# SAME54-board.net
KiCad netlist of a schematic drawn in EAGLE
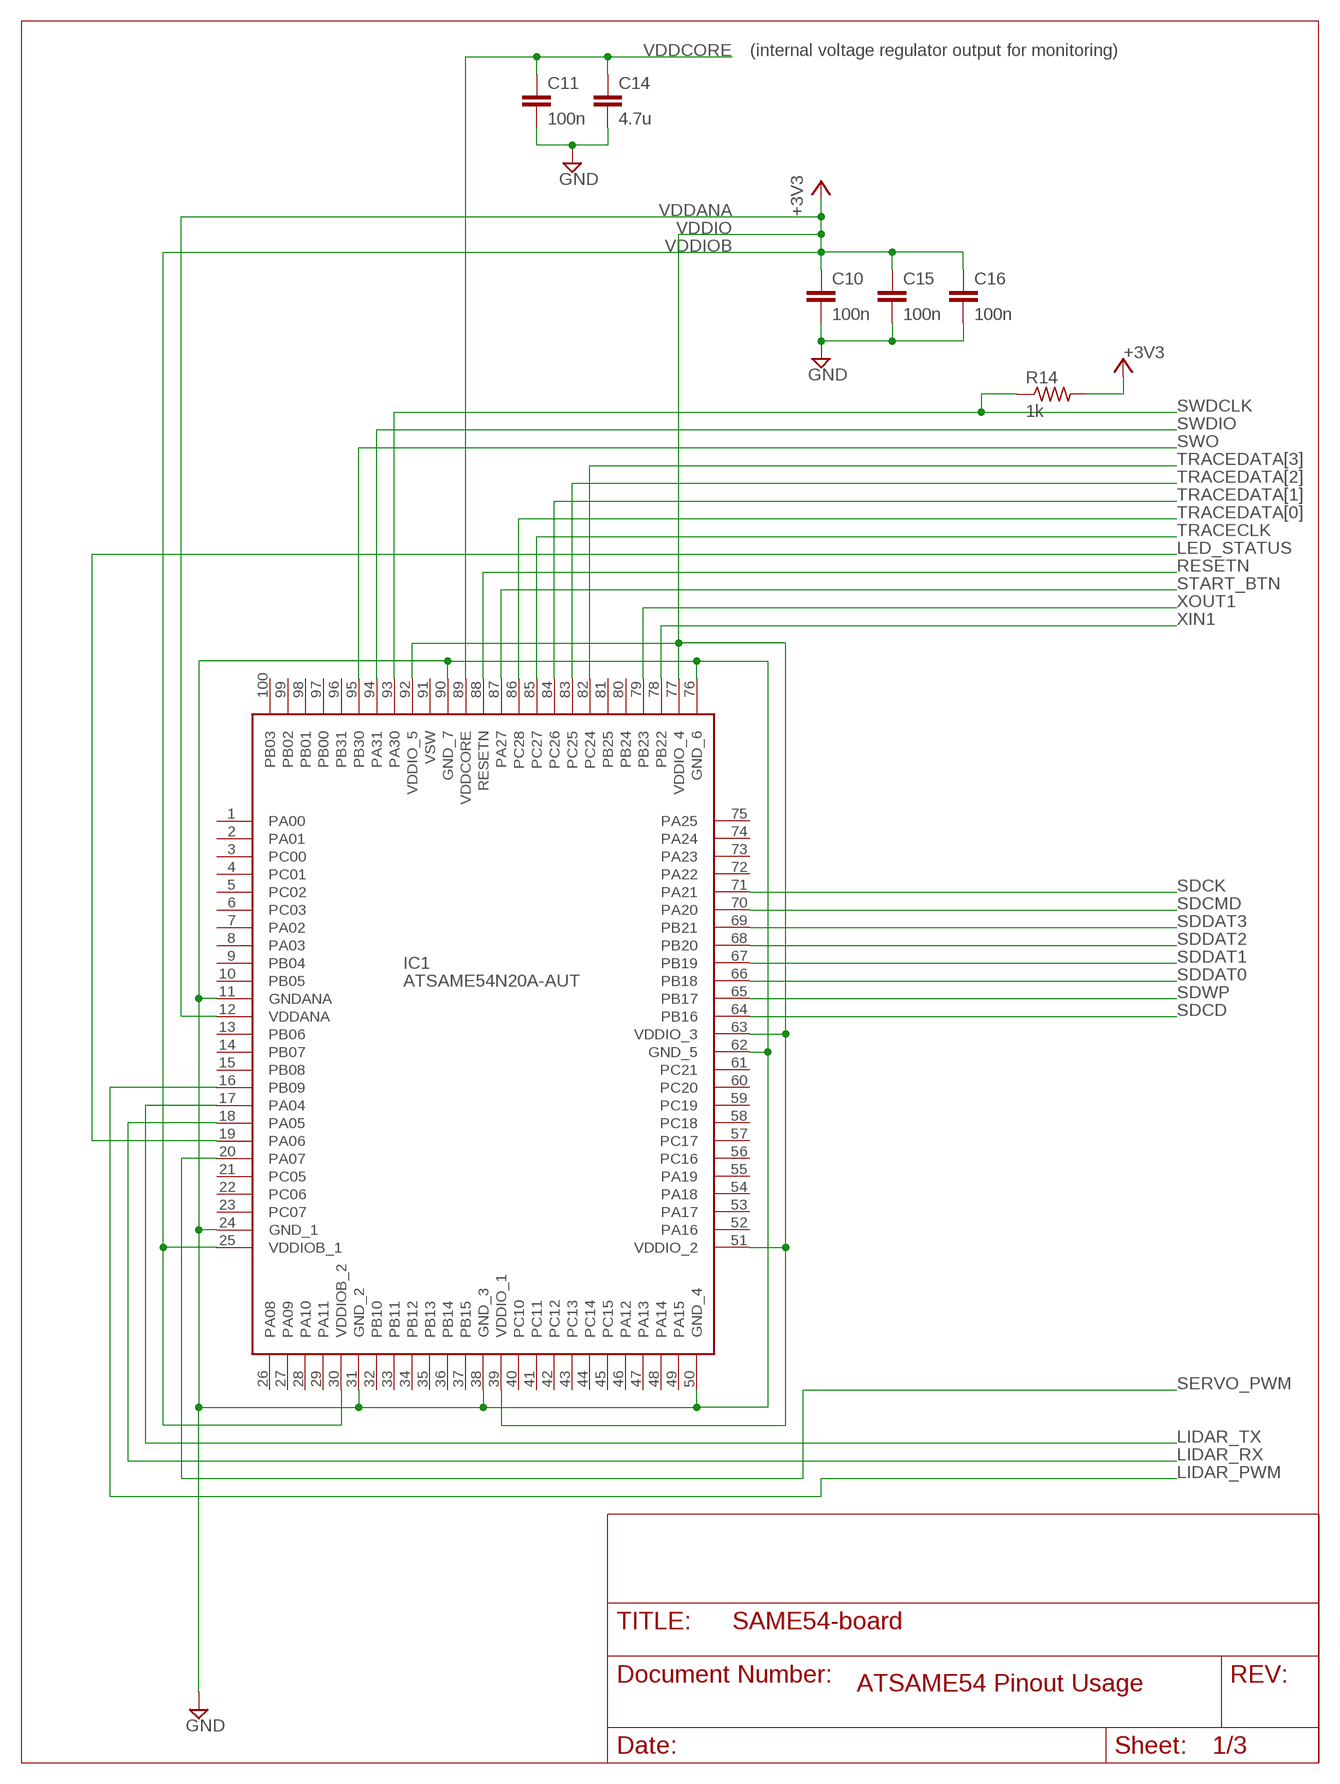
[diagram p0: schematic, sheet 1]
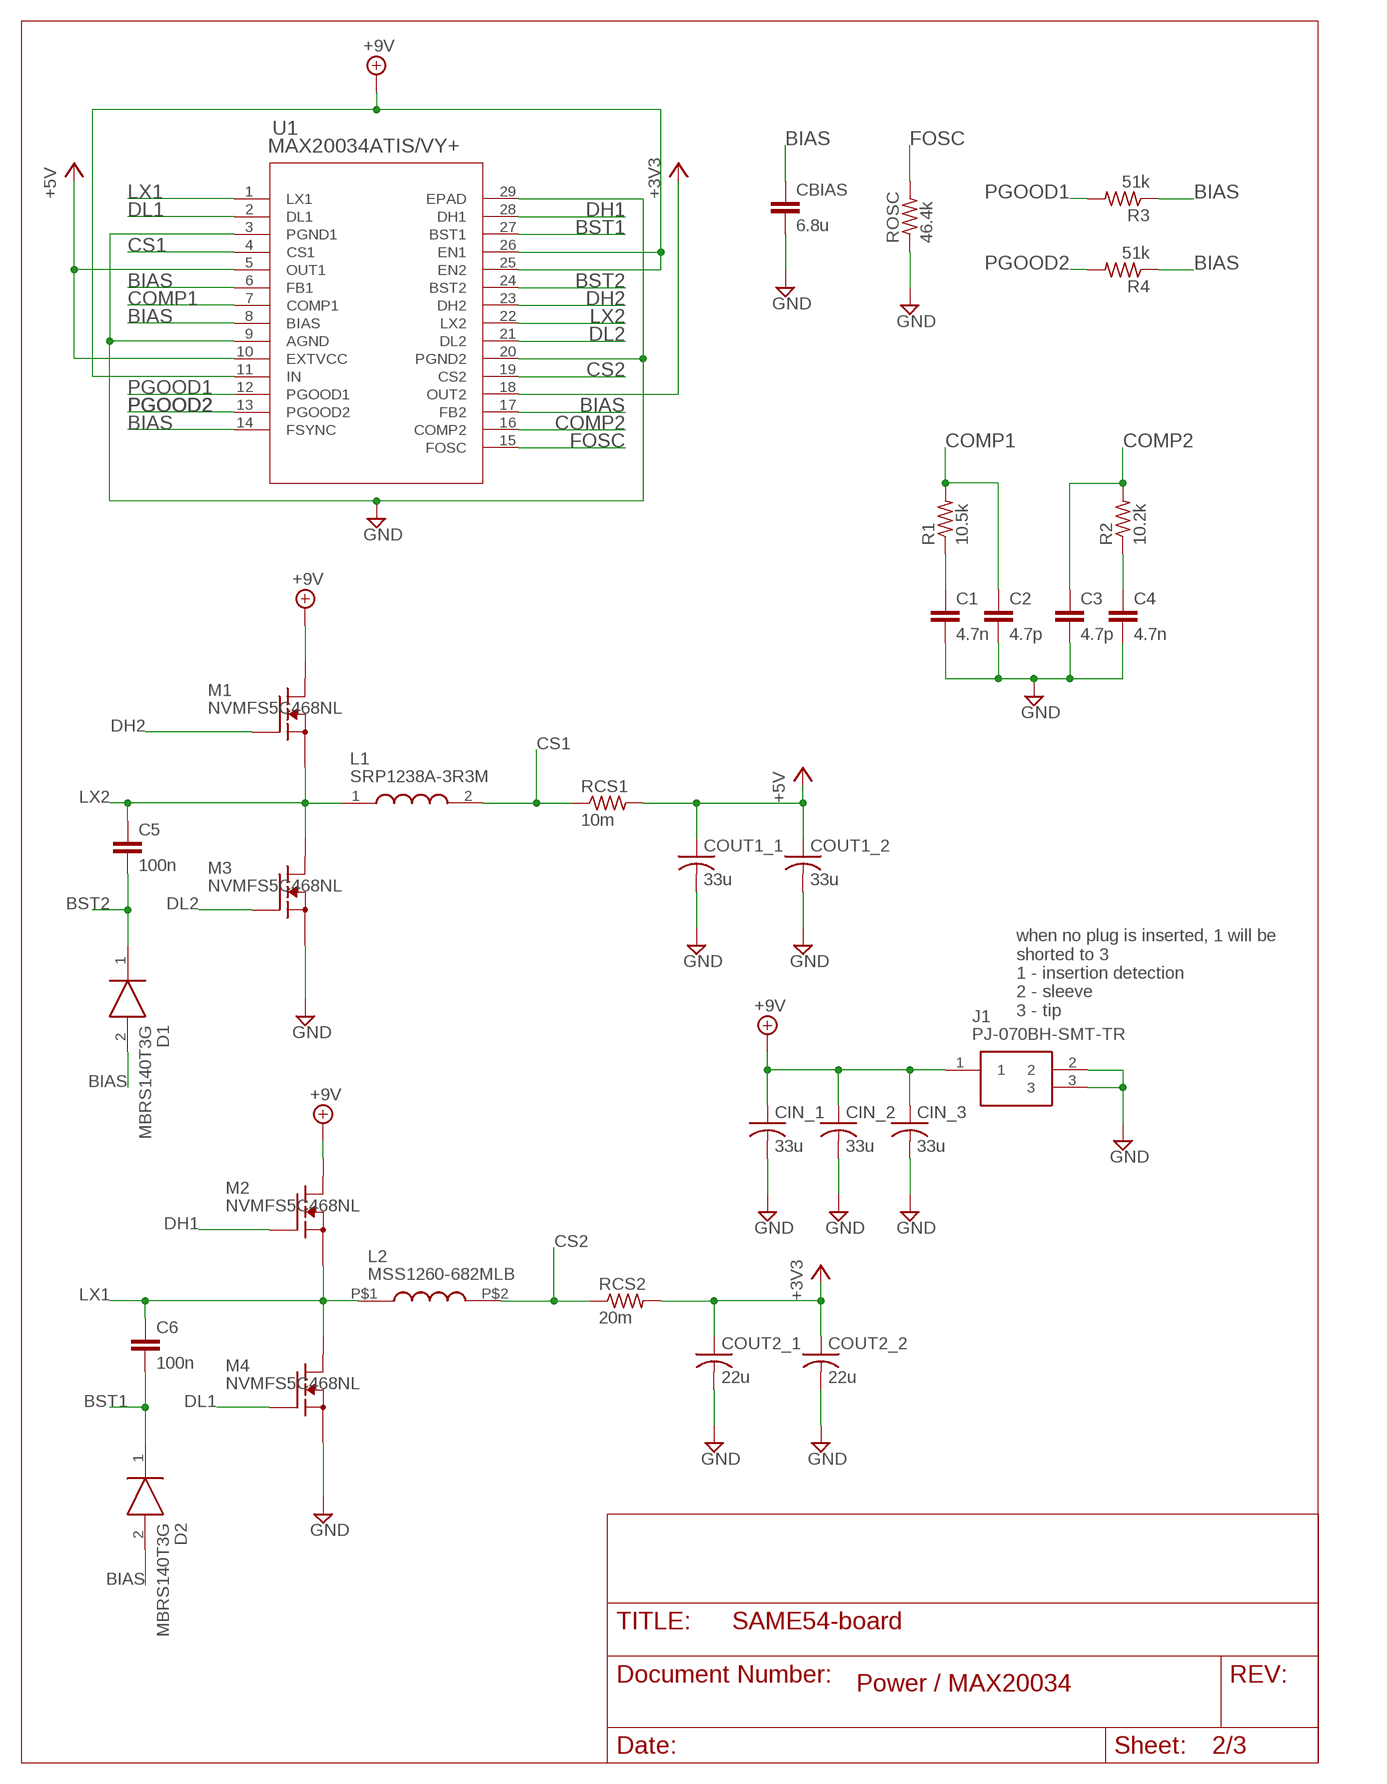
[diagram p1: schematic, sheet 2]
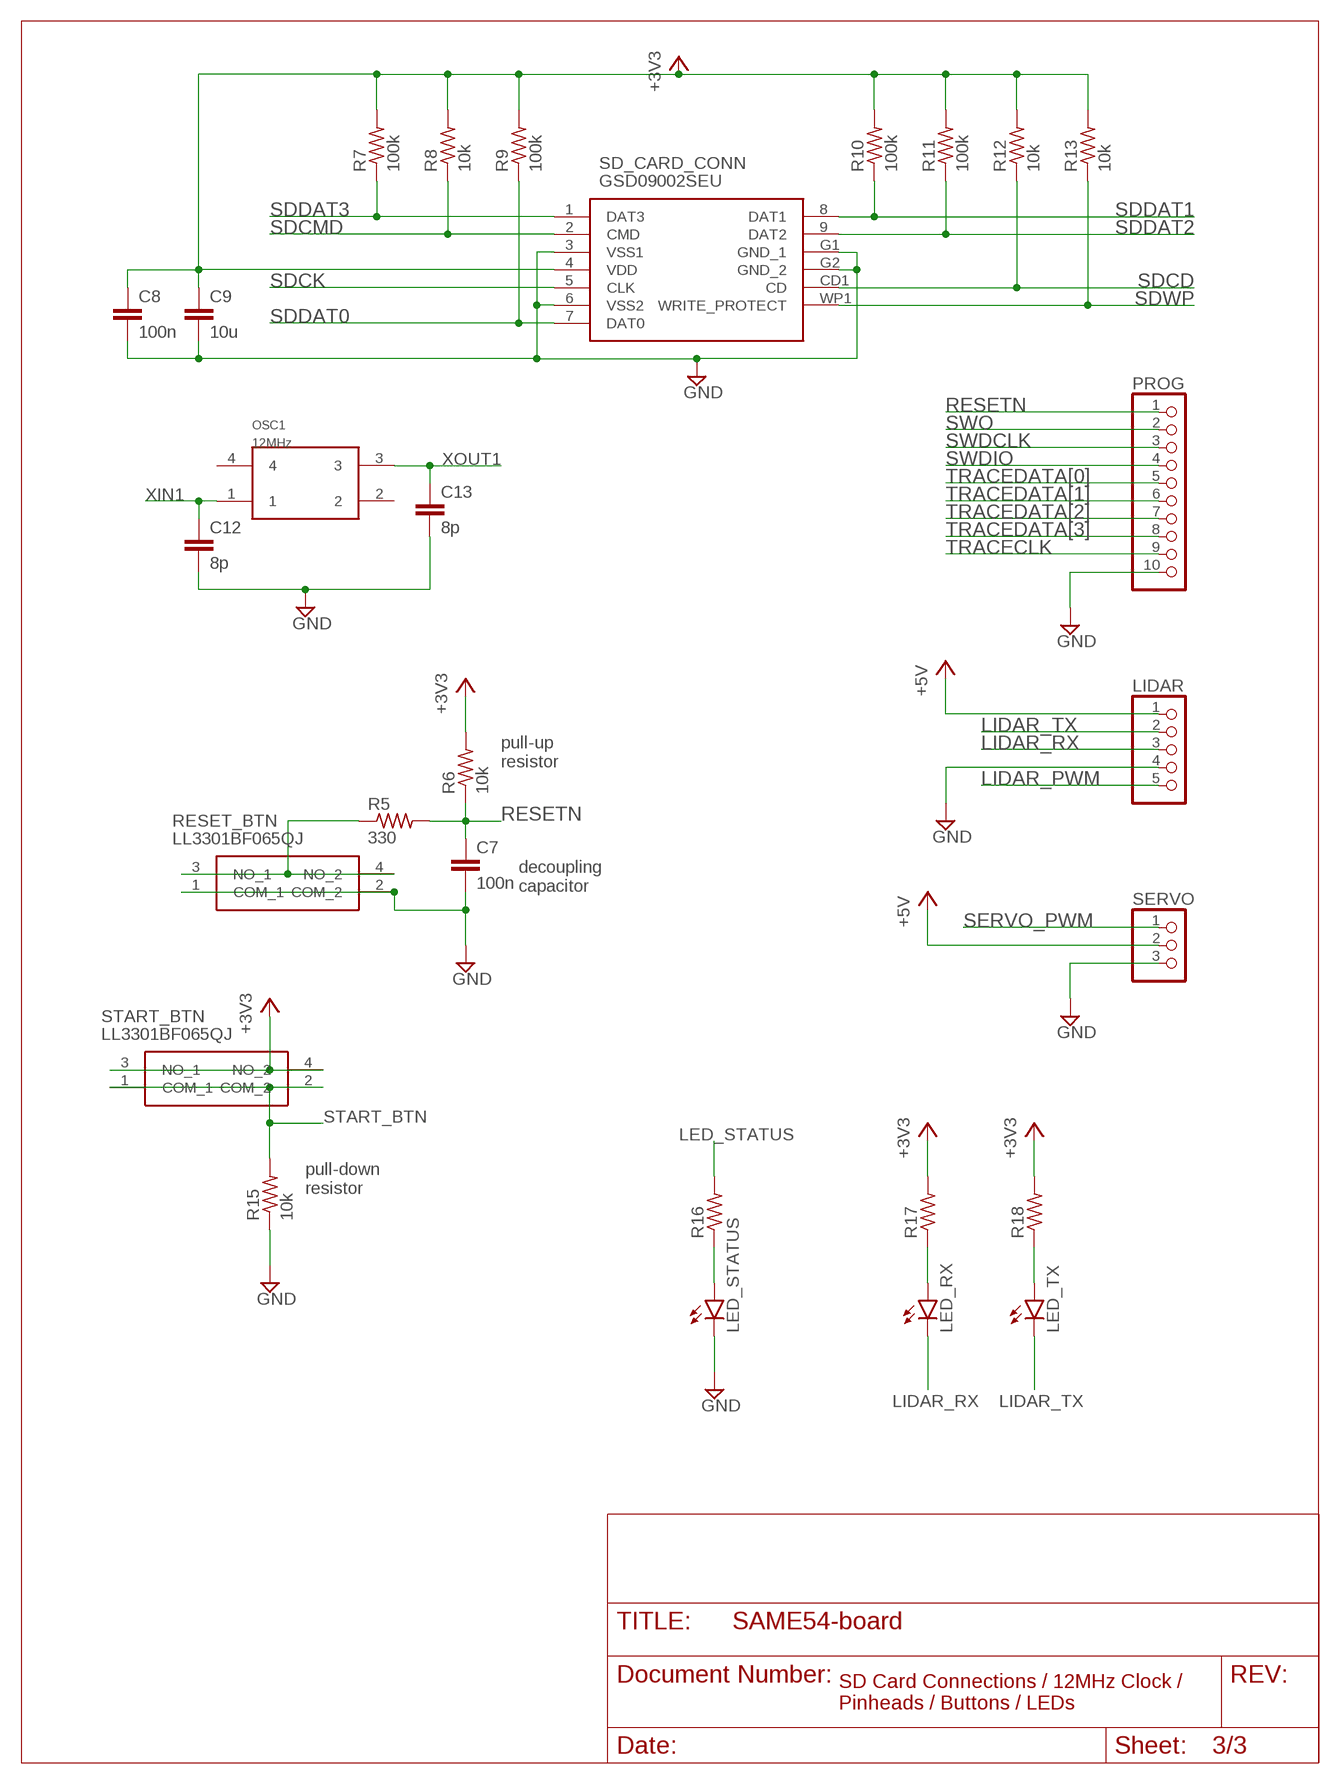
[diagram p2: schematic, sheet 3]

(export (version "E")
  (design (tool "Eeschema 10.0.6"))
  (components
    (comp (ref "C10")
      (value "100n")
      (footprint "eagle-import:C0603")
      (libsource (lib "eagle-import") (part "C-EUC0603"))
    )
    (comp (ref "C11")
      (value "100n")
      (footprint "eagle-import:C0603")
      (libsource (lib "eagle-import") (part "C-EUC0603"))
    )
    (comp (ref "C14")
      (value "4.7u")
      (footprint "eagle-import:C0603")
      (libsource (lib "eagle-import") (part "C-EUC0603"))
    )
    (comp (ref "C15")
      (value "100n")
      (footprint "eagle-import:C0603")
      (libsource (lib "eagle-import") (part "C-EUC0603"))
    )
    (comp (ref "C16")
      (value "100n")
      (footprint "eagle-import:C0603")
      (libsource (lib "eagle-import") (part "C-EUC0603"))
    )
    (comp (ref "IC1")
      (value "ATSAME54N20A-AUT")
      (footprint "eagle-import:QFP50P1600X1600X120-100N")
      (fields (field (name "MOUSER_PART_NUMBER") "556-ATSAME54N20AAUT"))
      (libsource (lib "eagle-import") (part "ATSAME54N20A-AUT"))
    )
    (comp (ref "R14")
      (value "1k")
      (footprint "eagle-import:R0603")
      (libsource (lib "eagle-import") (part "R-US_R0603"))
    )
    (comp (ref "C1")
      (value "4.7n")
      (footprint "eagle-import:C0603")
      (libsource (lib "eagle-import") (part "C-EUC0603"))
    )
    (comp (ref "C2")
      (value "4.7p")
      (footprint "eagle-import:C0402")
      (libsource (lib "eagle-import") (part "C-EUC0402"))
    )
    (comp (ref "C3")
      (value "4.7p")
      (footprint "eagle-import:C0402")
      (libsource (lib "eagle-import") (part "C-EUC0402"))
    )
    (comp (ref "C4")
      (value "4.7n")
      (footprint "eagle-import:C0603")
      (libsource (lib "eagle-import") (part "C-EUC0603"))
    )
    (comp (ref "C5")
      (value "100n")
      (footprint "eagle-import:C0603")
      (libsource (lib "eagle-import") (part "C-EUC0603"))
    )
    (comp (ref "C6")
      (value "100n")
      (footprint "eagle-import:C0603")
      (libsource (lib "eagle-import") (part "C-EUC0603"))
    )
    (comp (ref "CBIAS")
      (value "6.8u")
      (footprint "eagle-import:C1206")
      (libsource (lib "eagle-import") (part "C-EUC1206"))
    )
    (comp (ref "CIN_1")
      (value "33u")
      (footprint "eagle-import:C1812")
      (libsource (lib "eagle-import") (part "C-USC1812"))
    )
    (comp (ref "CIN_2")
      (value "33u")
      (footprint "eagle-import:C1812")
      (libsource (lib "eagle-import") (part "C-USC1812"))
    )
    (comp (ref "CIN_3")
      (value "33u")
      (footprint "eagle-import:C1812")
      (libsource (lib "eagle-import") (part "C-USC1812"))
    )
    (comp (ref "COUT1_1")
      (value "33u")
      (footprint "eagle-import:C1812")
      (libsource (lib "eagle-import") (part "C-USC1812"))
    )
    (comp (ref "COUT1_2")
      (value "33u")
      (footprint "eagle-import:C1812")
      (libsource (lib "eagle-import") (part "C-USC1812"))
    )
    (comp (ref "COUT2_1")
      (value "22u")
      (footprint "eagle-import:C1206")
      (libsource (lib "eagle-import") (part "C-USC1206"))
    )
    (comp (ref "COUT2_2")
      (value "22u")
      (footprint "eagle-import:C1206")
      (libsource (lib "eagle-import") (part "C-USC1206"))
    )
    (comp (ref "D1")
      (value "MBRS140T3G")
      (footprint "eagle-import:DIOM5436X247N")
      (fields (field (name "MOUSER_PART_NUMBER") "863-MBRS140T3G"))
      (libsource (lib "eagle-import") (part "MBRS140T3G"))
    )
    (comp (ref "D2")
      (value "MBRS140T3G")
      (footprint "eagle-import:DIOM5436X247N")
      (fields (field (name "MOUSER_PART_NUMBER") "863-MBRS140T3G"))
      (libsource (lib "eagle-import") (part "MBRS140T3G"))
    )
    (comp (ref "J1")
      (value "PJ-070BH-SMT-TR")
      (footprint "eagle-import:PJ070BHSMTTR")
      (fields (field (name "MOUSER_PART_NUMBER") "490-PJ-070BH-SMT-TR"))
      (libsource (lib "eagle-import") (part "PJ-070BH-SMT-TR"))
    )
    (comp (ref "L1")
      (value "SRP1238A-3R3M")
      (footprint "eagle-import:INDPM135125X350N")
      (fields (field (name "MOUSER_PART_NUMBER") "652-SRP1238A-3R3M"))
      (libsource (lib "eagle-import") (part "SRP1238A-3R3M"))
    )
    (comp (ref "L2")
      (value "MSS1260-682MLB")
      (footprint "eagle-import:MSS1260")
      (libsource (lib "eagle-import") (part "MSS1260-682MLB"))
    )
    (comp (ref "M1")
      (value "NVMFS5C468NL")
      (footprint "eagle-import:DFN5_SO-8FL")
      (libsource (lib "eagle-import") (part "NVMFS5C468NL"))
    )
    (comp (ref "M2")
      (value "NVMFS5C468NL")
      (footprint "eagle-import:DFN5_SO-8FL")
      (libsource (lib "eagle-import") (part "NVMFS5C468NL"))
    )
    (comp (ref "M3")
      (value "NVMFS5C468NL")
      (footprint "eagle-import:DFN5_SO-8FL")
      (libsource (lib "eagle-import") (part "NVMFS5C468NL"))
    )
    (comp (ref "M4")
      (value "NVMFS5C468NL")
      (footprint "eagle-import:DFN5_SO-8FL")
      (libsource (lib "eagle-import") (part "NVMFS5C468NL"))
    )
    (comp (ref "R1")
      (value "10.5k")
      (footprint "eagle-import:R0402")
      (libsource (lib "eagle-import") (part "R-US_R0402"))
    )
    (comp (ref "R2")
      (value "10.2k")
      (footprint "eagle-import:R0402")
      (libsource (lib "eagle-import") (part "R-US_R0402"))
    )
    (comp (ref "R3")
      (value "51k")
      (footprint "eagle-import:R0402")
      (libsource (lib "eagle-import") (part "R-US_R0402"))
    )
    (comp (ref "R4")
      (value "51k")
      (footprint "eagle-import:R0402")
      (libsource (lib "eagle-import") (part "R-US_R0402"))
    )
    (comp (ref "RCS1")
      (value "10m")
      (footprint "eagle-import:R0603")
      (libsource (lib "eagle-import") (part "R-US_R0603"))
    )
    (comp (ref "RCS2")
      (value "20m")
      (footprint "eagle-import:R1206")
      (libsource (lib "eagle-import") (part "R-US_R1206"))
    )
    (comp (ref "ROSC")
      (value "46.4k")
      (footprint "eagle-import:R0402")
      (libsource (lib "eagle-import") (part "R-US_R0402"))
    )
    (comp (ref "U1")
      (value "MAX20034ATIS/VY+")
      (footprint "eagle-import:21-100130_MXM")
      (fields (field (name "MANUFACTURER_PART_NUMBER") "MAX20034ATISVY+"))
      (libsource (lib "eagle-import") (part "MAX20034ATIS/VY+"))
    )
    (comp (ref "C7")
      (value "100n")
      (footprint "eagle-import:C0603")
      (libsource (lib "eagle-import") (part "C-EUC0603"))
    )
    (comp (ref "C8")
      (value "100n")
      (footprint "eagle-import:C0603")
      (libsource (lib "eagle-import") (part "C-EUC0603"))
    )
    (comp (ref "C9")
      (value "10u")
      (footprint "eagle-import:C0603")
      (libsource (lib "eagle-import") (part "C-EUC0603"))
    )
    (comp (ref "C12")
      (value "8p")
      (footprint "eagle-import:C0603")
      (libsource (lib "eagle-import") (part "C-EUC0603"))
    )
    (comp (ref "C13")
      (value "8p")
      (footprint "eagle-import:C0603")
      (libsource (lib "eagle-import") (part "C-EUC0603"))
    )
    (comp (ref "LED_RX")
      (value "LEDCHIPLED_0603")
      (footprint "eagle-import:CHIPLED_0603")
      (libsource (lib "eagle-import") (part "LEDCHIPLED_0603"))
    )
    (comp (ref "LED_STATUS")
      (value "LEDCHIPLED_0603")
      (footprint "eagle-import:CHIPLED_0603")
      (libsource (lib "eagle-import") (part "LEDCHIPLED_0603"))
    )
    (comp (ref "LED_TX")
      (value "LEDCHIPLED_0603")
      (footprint "eagle-import:CHIPLED_0603")
      (libsource (lib "eagle-import") (part "LEDCHIPLED_0603"))
    )
    (comp (ref "LIDAR")
      (value "PINHD-1X5")
      (footprint "eagle-import:1X05")
      (libsource (lib "eagle-import") (part "PINHD-1X5"))
    )
    (comp (ref "OSC1")
      (value "CX3225CA12000D0KPSC1CX3225CA")
      (footprint "eagle-import:OSCCC320X250X90N")
      (libsource (lib "eagle-import") (part "CX3225CA12000D0KPSC1CX3225CA"))
    )
    (comp (ref "PROG")
      (value "PINHD-1X10")
      (footprint "eagle-import:1X10")
      (libsource (lib "eagle-import") (part "PINHD-1X10"))
    )
    (comp (ref "R5")
      (value "330")
      (footprint "eagle-import:R0603")
      (libsource (lib "eagle-import") (part "R-US_R0603"))
    )
    (comp (ref "R6")
      (value "10k")
      (footprint "eagle-import:R0603")
      (libsource (lib "eagle-import") (part "R-US_R0603"))
    )
    (comp (ref "R7")
      (value "100k")
      (footprint "eagle-import:R0603")
      (libsource (lib "eagle-import") (part "R-US_R0603"))
    )
    (comp (ref "R8")
      (value "10k")
      (footprint "eagle-import:R0603")
      (libsource (lib "eagle-import") (part "R-US_R0603"))
    )
    (comp (ref "R9")
      (value "100k")
      (footprint "eagle-import:R0603")
      (libsource (lib "eagle-import") (part "R-US_R0603"))
    )
    (comp (ref "R10")
      (value "100k")
      (footprint "eagle-import:R0603")
      (libsource (lib "eagle-import") (part "R-US_R0603"))
    )
    (comp (ref "R11")
      (value "100k")
      (footprint "eagle-import:R0603")
      (libsource (lib "eagle-import") (part "R-US_R0603"))
    )
    (comp (ref "R12")
      (value "10k")
      (footprint "eagle-import:R0603")
      (libsource (lib "eagle-import") (part "R-US_R0603"))
    )
    (comp (ref "R13")
      (value "10k")
      (footprint "eagle-import:R0603")
      (libsource (lib "eagle-import") (part "R-US_R0603"))
    )
    (comp (ref "R15")
      (value "10k")
      (footprint "eagle-import:R0603")
      (libsource (lib "eagle-import") (part "R-US_R0603"))
    )
    (comp (ref "R16")
      (value "R-US_R0603")
      (footprint "eagle-import:R0603")
      (libsource (lib "eagle-import") (part "R-US_R0603"))
    )
    (comp (ref "R17")
      (value "R-US_R0603")
      (footprint "eagle-import:R0603")
      (libsource (lib "eagle-import") (part "R-US_R0603"))
    )
    (comp (ref "R18")
      (value "R-US_R0603")
      (footprint "eagle-import:R0603")
      (libsource (lib "eagle-import") (part "R-US_R0603"))
    )
    (comp (ref "RESET_BTN")
      (value "LL3301BF065QJ")
      (footprint "eagle-import:LL3301BF065QJ")
      (fields (field (name "MOUSER_PART_NUMBER") "612-LL3301BF065QJ"))
      (libsource (lib "eagle-import") (part "LL3301BF065QJ"))
    )
    (comp (ref "SD_CARD_CONN")
      (value "GSD09002SEU")
      (footprint "eagle-import:GSD09002SEU")
      (fields (field (name "MOUSER_PART_NUMBER") "523-GSD09002SEU"))
      (libsource (lib "eagle-import") (part "GSD09002SEU"))
    )
    (comp (ref "SERVO")
      (value "PINHD-1X3")
      (footprint "eagle-import:1X03")
      (libsource (lib "eagle-import") (part "PINHD-1X3"))
    )
    (comp (ref "START_BTN")
      (value "LL3301BF065QJ")
      (footprint "eagle-import:LL3301BF065QJ")
      (fields (field (name "MOUSER_PART_NUMBER") "612-LL3301BF065QJ"))
      (libsource (lib "eagle-import") (part "LL3301BF065QJ"))
    )
  )
  (nets
    (net (code "1") (name "+3V3") (class "Default")
      (node (ref "C10") (pin "1") (pinfunction "1_1") (pintype "passive"))
      (node (ref "C15") (pin "1") (pinfunction "1_1") (pintype "passive"))
      (node (ref "C16") (pin "1") (pinfunction "1_1") (pintype "passive"))
      (node (ref "C8") (pin "1") (pinfunction "1_1") (pintype "passive"))
      (node (ref "C9") (pin "1") (pinfunction "1_1") (pintype "passive"))
      (node (ref "COUT2_1") (pin "1") (pinfunction "1_1") (pintype "passive"))
      (node (ref "COUT2_2") (pin "1") (pinfunction "1_1") (pintype "passive"))
      (node (ref "IC1") (pin "12") (pinfunction "VDDANA_12") (pintype "bidirectional"))
      (node (ref "IC1") (pin "25") (pinfunction "VDDIOB_1_25") (pintype "bidirectional"))
      (node (ref "IC1") (pin "30") (pinfunction "VDDIOB_2_30") (pintype "bidirectional"))
      (node (ref "IC1") (pin "39") (pinfunction "VDDIO_1_39") (pintype "bidirectional"))
      (node (ref "IC1") (pin "51") (pinfunction "VDDIO_2_51") (pintype "bidirectional"))
      (node (ref "IC1") (pin "63") (pinfunction "VDDIO_3_63") (pintype "bidirectional"))
      (node (ref "IC1") (pin "77") (pinfunction "VDDIO_4_77") (pintype "bidirectional"))
      (node (ref "IC1") (pin "92") (pinfunction "VDDIO_5_92") (pintype "bidirectional"))
      (node (ref "R10") (pin "2") (pinfunction "2_2") (pintype "passive"))
      (node (ref "R11") (pin "2") (pinfunction "2_2") (pintype "passive"))
      (node (ref "R12") (pin "2") (pinfunction "2_2") (pintype "passive"))
      (node (ref "R13") (pin "2") (pinfunction "2_2") (pintype "passive"))
      (node (ref "R14") (pin "2") (pinfunction "2_2") (pintype "passive"))
      (node (ref "R17") (pin "2") (pinfunction "2_2") (pintype "passive"))
      (node (ref "R18") (pin "2") (pinfunction "2_2") (pintype "passive"))
      (node (ref "R6") (pin "2") (pinfunction "2_2") (pintype "passive"))
      (node (ref "R7") (pin "2") (pinfunction "2_2") (pintype "passive"))
      (node (ref "R8") (pin "2") (pinfunction "2_2") (pintype "passive"))
      (node (ref "R9") (pin "2") (pinfunction "2_2") (pintype "passive"))
      (node (ref "RCS2") (pin "2") (pinfunction "2_2") (pintype "passive"))
      (node (ref "SD_CARD_CONN") (pin "4") (pinfunction "VDD_4") (pintype "bidirectional"))
      (node (ref "START_BTN") (pin "3") (pinfunction "NO_1_3") (pintype "bidirectional"))
      (node (ref "START_BTN") (pin "4") (pinfunction "NO_2_4") (pintype "bidirectional"))
      (node (ref "U1") (pin "18") (pinfunction "OUT2_18") (pintype "output"))
    )
    (net (code "2") (name "+5V") (class "Default")
      (node (ref "COUT1_1") (pin "1") (pinfunction "1_1") (pintype "passive"))
      (node (ref "COUT1_2") (pin "1") (pinfunction "1_1") (pintype "passive"))
      (node (ref "LIDAR") (pin "1") (pinfunction "1_1") (pintype "passive"))
      (node (ref "RCS1") (pin "2") (pinfunction "2_2") (pintype "passive"))
      (node (ref "SERVO") (pin "2") (pinfunction "2_2") (pintype "passive"))
      (node (ref "U1") (pin "10") (pinfunction "EXTVCC_10") (pintype "input"))
      (node (ref "U1") (pin "5") (pinfunction "OUT1_5") (pintype "output"))
    )
    (net (code "3") (name "+9V") (class "Default")
      (node (ref "CIN_1") (pin "1") (pinfunction "1_1") (pintype "passive"))
      (node (ref "CIN_2") (pin "1") (pinfunction "1_1") (pintype "passive"))
      (node (ref "CIN_3") (pin "1") (pinfunction "1_1") (pintype "passive"))
      (node (ref "J1") (pin "1") (pinfunction "1_1") (pintype "bidirectional"))
      (node (ref "M1") (pin "D1") (pinfunction "D_D1") (pintype "passive"))
      (node (ref "M1") (pin "D2") (pinfunction "D_D2") (pintype "passive"))
      (node (ref "M1") (pin "D3") (pinfunction "D_D3") (pintype "passive"))
      (node (ref "M1") (pin "D4") (pinfunction "D_D4") (pintype "passive"))
      (node (ref "M2") (pin "D1") (pinfunction "D_D1") (pintype "passive"))
      (node (ref "M2") (pin "D2") (pinfunction "D_D2") (pintype "passive"))
      (node (ref "M2") (pin "D3") (pinfunction "D_D3") (pintype "passive"))
      (node (ref "M2") (pin "D4") (pinfunction "D_D4") (pintype "passive"))
      (node (ref "U1") (pin "11") (pinfunction "IN_11") (pintype "input"))
      (node (ref "U1") (pin "25") (pinfunction "EN2_25") (pintype "input"))
      (node (ref "U1") (pin "26") (pinfunction "EN1_26") (pintype "input"))
    )
    (net (code "4") (name "BIAS") (class "Default")
      (node (ref "CBIAS") (pin "1") (pinfunction "1_1") (pintype "passive"))
      (node (ref "D1") (pin "2") (pinfunction "A_2") (pintype "bidirectional"))
      (node (ref "D2") (pin "2") (pinfunction "A_2") (pintype "bidirectional"))
      (node (ref "R3") (pin "1") (pinfunction "1_1") (pintype "passive"))
      (node (ref "R4") (pin "1") (pinfunction "1_1") (pintype "passive"))
      (node (ref "U1") (pin "14") (pinfunction "FSYNC_14") (pintype "input"))
      (node (ref "U1") (pin "17") (pinfunction "FB2_17") (pintype "input"))
      (node (ref "U1") (pin "6") (pinfunction "FB1_6") (pintype "input"))
      (node (ref "U1") (pin "8") (pinfunction "BIAS_8") (pintype "output"))
    )
    (net (code "5") (name "BST1") (class "Default")
      (node (ref "C6") (pin "2") (pinfunction "2_2") (pintype "passive"))
      (node (ref "D2") (pin "1") (pinfunction "K_1") (pintype "bidirectional"))
      (node (ref "U1") (pin "27") (pinfunction "BST1_27") (pintype "passive"))
    )
    (net (code "6") (name "BST2") (class "Default")
      (node (ref "C5") (pin "2") (pinfunction "2_2") (pintype "passive"))
      (node (ref "D1") (pin "1") (pinfunction "K_1") (pintype "bidirectional"))
      (node (ref "U1") (pin "24") (pinfunction "BST2_24") (pintype "passive"))
    )
    (net (code "7") (name "COMP1") (class "Default")
      (node (ref "C2") (pin "1") (pinfunction "1_1") (pintype "passive"))
      (node (ref "R1") (pin "2") (pinfunction "2_2") (pintype "passive"))
      (node (ref "U1") (pin "7") (pinfunction "COMP1_7") (pintype "output"))
    )
    (net (code "8") (name "COMP2") (class "Default")
      (node (ref "C3") (pin "1") (pinfunction "1_1") (pintype "passive"))
      (node (ref "R2") (pin "2") (pinfunction "2_2") (pintype "passive"))
      (node (ref "U1") (pin "16") (pinfunction "COMP2_16") (pintype "output"))
    )
    (net (code "9") (name "CS1") (class "Default")
      (node (ref "L1") (pin "2") (pinfunction "2_2") (pintype "bidirectional"))
      (node (ref "RCS1") (pin "1") (pinfunction "1_1") (pintype "passive"))
      (node (ref "U1") (pin "4") (pinfunction "CS1_4") (pintype "input"))
    )
    (net (code "10") (name "CS2") (class "Default")
      (node (ref "L2") (pin "P$2") (pinfunction "2_P$2") (pintype "bidirectional"))
      (node (ref "RCS2") (pin "1") (pinfunction "1_1") (pintype "passive"))
      (node (ref "U1") (pin "19") (pinfunction "CS2_19") (pintype "input"))
    )
    (net (code "11") (name "DH1") (class "Default")
      (node (ref "M2") (pin "G") (pinfunction "G_G") (pintype "passive"))
      (node (ref "U1") (pin "28") (pinfunction "DH1_28") (pintype "output"))
    )
    (net (code "12") (name "DH2") (class "Default")
      (node (ref "M1") (pin "G") (pinfunction "G_G") (pintype "passive"))
      (node (ref "U1") (pin "23") (pinfunction "DH2_23") (pintype "output"))
    )
    (net (code "13") (name "DL1") (class "Default")
      (node (ref "M4") (pin "G") (pinfunction "G_G") (pintype "passive"))
      (node (ref "U1") (pin "2") (pinfunction "DL1_2") (pintype "output"))
    )
    (net (code "14") (name "DL2") (class "Default")
      (node (ref "M3") (pin "G") (pinfunction "G_G") (pintype "passive"))
      (node (ref "U1") (pin "21") (pinfunction "DL2_21") (pintype "output"))
    )
    (net (code "15") (name "FOSC") (class "Default")
      (node (ref "ROSC") (pin "2") (pinfunction "2_2") (pintype "passive"))
      (node (ref "U1") (pin "15") (pinfunction "FOSC_15") (pintype "input"))
    )
    (net (code "16") (name "GND") (class "Default")
      (node (ref "C1") (pin "2") (pinfunction "2_2") (pintype "passive"))
      (node (ref "C10") (pin "2") (pinfunction "2_2") (pintype "passive"))
      (node (ref "C11") (pin "2") (pinfunction "2_2") (pintype "passive"))
      (node (ref "C12") (pin "2") (pinfunction "2_2") (pintype "passive"))
      (node (ref "C13") (pin "2") (pinfunction "2_2") (pintype "passive"))
      (node (ref "C14") (pin "2") (pinfunction "2_2") (pintype "passive"))
      (node (ref "C15") (pin "2") (pinfunction "2_2") (pintype "passive"))
      (node (ref "C16") (pin "2") (pinfunction "2_2") (pintype "passive"))
      (node (ref "C2") (pin "2") (pinfunction "2_2") (pintype "passive"))
      (node (ref "C3") (pin "2") (pinfunction "2_2") (pintype "passive"))
      (node (ref "C4") (pin "2") (pinfunction "2_2") (pintype "passive"))
      (node (ref "C7") (pin "2") (pinfunction "2_2") (pintype "passive"))
      (node (ref "C8") (pin "2") (pinfunction "2_2") (pintype "passive"))
      (node (ref "C9") (pin "2") (pinfunction "2_2") (pintype "passive"))
      (node (ref "CBIAS") (pin "2") (pinfunction "2_2") (pintype "passive"))
      (node (ref "CIN_1") (pin "2") (pinfunction "2_2") (pintype "passive"))
      (node (ref "CIN_2") (pin "2") (pinfunction "2_2") (pintype "passive"))
      (node (ref "CIN_3") (pin "2") (pinfunction "2_2") (pintype "passive"))
      (node (ref "COUT1_1") (pin "2") (pinfunction "2_2") (pintype "passive"))
      (node (ref "COUT1_2") (pin "2") (pinfunction "2_2") (pintype "passive"))
      (node (ref "COUT2_1") (pin "2") (pinfunction "2_2") (pintype "passive"))
      (node (ref "COUT2_2") (pin "2") (pinfunction "2_2") (pintype "passive"))
      (node (ref "IC1") (pin "11") (pinfunction "GNDANA_11") (pintype "bidirectional"))
      (node (ref "IC1") (pin "24") (pinfunction "GND_1_24") (pintype "bidirectional"))
      (node (ref "IC1") (pin "31") (pinfunction "GND_2_31") (pintype "bidirectional"))
      (node (ref "IC1") (pin "38") (pinfunction "GND_3_38") (pintype "bidirectional"))
      (node (ref "IC1") (pin "50") (pinfunction "GND_4_50") (pintype "bidirectional"))
      (node (ref "IC1") (pin "62") (pinfunction "GND_5_62") (pintype "bidirectional"))
      (node (ref "IC1") (pin "76") (pinfunction "GND_6_76") (pintype "bidirectional"))
      (node (ref "IC1") (pin "90") (pinfunction "GND_7_90") (pintype "bidirectional"))
      (node (ref "J1") (pin "2") (pinfunction "2_2") (pintype "bidirectional"))
      (node (ref "J1") (pin "3") (pinfunction "3_3") (pintype "bidirectional"))
      (node (ref "LED_STATUS") (pin "C") (pinfunction "C_C") (pintype "passive"))
      (node (ref "LIDAR") (pin "4") (pinfunction "4_4") (pintype "passive"))
      (node (ref "M3") (pin "S1") (pinfunction "S_S1") (pintype "passive"))
      (node (ref "M3") (pin "S2") (pinfunction "S_S2") (pintype "passive"))
      (node (ref "M3") (pin "S3") (pinfunction "S_S3") (pintype "passive"))
      (node (ref "M4") (pin "S1") (pinfunction "S_S1") (pintype "passive"))
      (node (ref "M4") (pin "S2") (pinfunction "S_S2") (pintype "passive"))
      (node (ref "M4") (pin "S3") (pinfunction "S_S3") (pintype "passive"))
      (node (ref "PROG") (pin "10") (pinfunction "10_10") (pintype "passive"))
      (node (ref "R15") (pin "1") (pinfunction "1_1") (pintype "passive"))
      (node (ref "RESET_BTN") (pin "1") (pinfunction "COM_1_1") (pintype "bidirectional"))
      (node (ref "RESET_BTN") (pin "2") (pinfunction "COM_2_2") (pintype "bidirectional"))
      (node (ref "ROSC") (pin "1") (pinfunction "1_1") (pintype "passive"))
      (node (ref "SD_CARD_CONN") (pin "3") (pinfunction "VSS1_3") (pintype "bidirectional"))
      (node (ref "SD_CARD_CONN") (pin "6") (pinfunction "VSS2_6") (pintype "bidirectional"))
      (node (ref "SD_CARD_CONN") (pin "G1") (pinfunction "GND_1_G1") (pintype "bidirectional"))
      (node (ref "SD_CARD_CONN") (pin "G2") (pinfunction "GND_2_G2") (pintype "bidirectional"))
      (node (ref "SERVO") (pin "3") (pinfunction "3_3") (pintype "passive"))
      (node (ref "U1") (pin "20") (pinfunction "PGND2_20") (pintype "power_in"))
      (node (ref "U1") (pin "29") (pinfunction "EPAD_29") (pintype "power_in"))
      (node (ref "U1") (pin "3") (pinfunction "PGND1_3") (pintype "power_in"))
      (node (ref "U1") (pin "9") (pinfunction "AGND_9") (pintype "power_in"))
    )
    (net (code "17") (name "LED_STATUS") (class "Default")
      (node (ref "IC1") (pin "19") (pinfunction "PA06_19") (pintype "bidirectional"))
      (node (ref "R16") (pin "2") (pinfunction "2_2") (pintype "passive"))
    )
    (net (code "18") (name "LIDAR_PWM") (class "Default")
      (node (ref "IC1") (pin "16") (pinfunction "PB09_16") (pintype "bidirectional"))
      (node (ref "LIDAR") (pin "5") (pinfunction "5_5") (pintype "passive"))
    )
    (net (code "19") (name "LIDAR_RX") (class "Default")
      (node (ref "IC1") (pin "18") (pinfunction "PA05_18") (pintype "bidirectional"))
      (node (ref "LED_RX") (pin "C") (pinfunction "C_C") (pintype "passive"))
      (node (ref "LIDAR") (pin "3") (pinfunction "3_3") (pintype "passive"))
    )
    (net (code "20") (name "LIDAR_TX") (class "Default")
      (node (ref "IC1") (pin "17") (pinfunction "PA04_17") (pintype "bidirectional"))
      (node (ref "LED_TX") (pin "C") (pinfunction "C_C") (pintype "passive"))
      (node (ref "LIDAR") (pin "2") (pinfunction "2_2") (pintype "passive"))
    )
    (net (code "21") (name "LX1") (class "Default")
      (node (ref "C6") (pin "1") (pinfunction "1_1") (pintype "passive"))
      (node (ref "L2") (pin "P$1") (pinfunction "1_P$1") (pintype "bidirectional"))
      (node (ref "M2") (pin "S1") (pinfunction "S_S1") (pintype "passive"))
      (node (ref "M2") (pin "S2") (pinfunction "S_S2") (pintype "passive"))
      (node (ref "M2") (pin "S3") (pinfunction "S_S3") (pintype "passive"))
      (node (ref "M4") (pin "D1") (pinfunction "D_D1") (pintype "passive"))
      (node (ref "M4") (pin "D2") (pinfunction "D_D2") (pintype "passive"))
      (node (ref "M4") (pin "D3") (pinfunction "D_D3") (pintype "passive"))
      (node (ref "M4") (pin "D4") (pinfunction "D_D4") (pintype "passive"))
      (node (ref "U1") (pin "1") (pinfunction "LX1_1") (pintype "passive"))
    )
    (net (code "22") (name "LX2") (class "Default")
      (node (ref "C5") (pin "1") (pinfunction "1_1") (pintype "passive"))
      (node (ref "L1") (pin "1") (pinfunction "1_1") (pintype "bidirectional"))
      (node (ref "M1") (pin "S1") (pinfunction "S_S1") (pintype "passive"))
      (node (ref "M1") (pin "S2") (pinfunction "S_S2") (pintype "passive"))
      (node (ref "M1") (pin "S3") (pinfunction "S_S3") (pintype "passive"))
      (node (ref "M3") (pin "D1") (pinfunction "D_D1") (pintype "passive"))
      (node (ref "M3") (pin "D2") (pinfunction "D_D2") (pintype "passive"))
      (node (ref "M3") (pin "D3") (pinfunction "D_D3") (pintype "passive"))
      (node (ref "M3") (pin "D4") (pinfunction "D_D4") (pintype "passive"))
      (node (ref "U1") (pin "22") (pinfunction "LX2_22") (pintype "passive"))
    )
    (net (code "23") (name "Net-(C1-Pad1)") (class "Default")
      (node (ref "C1") (pin "1") (pinfunction "1_1") (pintype "passive"))
      (node (ref "R1") (pin "1") (pinfunction "1_1") (pintype "passive"))
    )
    (net (code "24") (name "Net-(C4-Pad1)") (class "Default")
      (node (ref "C4") (pin "1") (pinfunction "1_1") (pintype "passive"))
      (node (ref "R2") (pin "1") (pinfunction "1_1") (pintype "passive"))
    )
    (net (code "25") (name "Net-(LED_RX-PadA)") (class "Default")
      (node (ref "LED_RX") (pin "A") (pinfunction "A_A") (pintype "passive"))
      (node (ref "R17") (pin "1") (pinfunction "1_1") (pintype "passive"))
    )
    (net (code "26") (name "Net-(LED_STATUS-PadA)") (class "Default")
      (node (ref "LED_STATUS") (pin "A") (pinfunction "A_A") (pintype "passive"))
      (node (ref "R16") (pin "1") (pinfunction "1_1") (pintype "passive"))
    )
    (net (code "27") (name "Net-(LED_TX-PadA)") (class "Default")
      (node (ref "LED_TX") (pin "A") (pinfunction "A_A") (pintype "passive"))
      (node (ref "R18") (pin "1") (pinfunction "1_1") (pintype "passive"))
    )
    (net (code "28") (name "Net-(RESET_BTN-NO_1)") (class "Default")
      (node (ref "R5") (pin "1") (pinfunction "1_1") (pintype "passive"))
      (node (ref "RESET_BTN") (pin "3") (pinfunction "NO_1_3") (pintype "bidirectional"))
      (node (ref "RESET_BTN") (pin "4") (pinfunction "NO_2_4") (pintype "bidirectional"))
    )
    (net (code "29") (name "PGOOD1") (class "Default")
      (node (ref "R3") (pin "2") (pinfunction "2_2") (pintype "passive"))
      (node (ref "U1") (pin "12") (pinfunction "PGOOD1_12") (pintype "output"))
    )
    (net (code "30") (name "PGOOD2") (class "Default")
      (node (ref "R4") (pin "2") (pinfunction "2_2") (pintype "passive"))
      (node (ref "U1") (pin "13") (pinfunction "PGOOD2_13") (pintype "output"))
    )
    (net (code "31") (name "RESETN") (class "Default")
      (node (ref "C7") (pin "1") (pinfunction "1_1") (pintype "passive"))
      (node (ref "IC1") (pin "88") (pinfunction "RESETN_88") (pintype "bidirectional"))
      (node (ref "PROG") (pin "1") (pinfunction "1_1") (pintype "passive"))
      (node (ref "R5") (pin "2") (pinfunction "2_2") (pintype "passive"))
      (node (ref "R6") (pin "1") (pinfunction "1_1") (pintype "passive"))
    )
    (net (code "32") (name "SDCD") (class "Default")
      (node (ref "IC1") (pin "64") (pinfunction "PB16_64") (pintype "bidirectional"))
      (node (ref "R12") (pin "1") (pinfunction "1_1") (pintype "passive"))
      (node (ref "SD_CARD_CONN") (pin "CD1") (pinfunction "CD_CD1") (pintype "bidirectional"))
    )
    (net (code "33") (name "SDCK") (class "Default")
      (node (ref "IC1") (pin "71") (pinfunction "PA21_71") (pintype "bidirectional"))
      (node (ref "SD_CARD_CONN") (pin "5") (pinfunction "CLK_5") (pintype "bidirectional"))
    )
    (net (code "34") (name "SDCMD") (class "Default")
      (node (ref "IC1") (pin "70") (pinfunction "PA20_70") (pintype "bidirectional"))
      (node (ref "R8") (pin "1") (pinfunction "1_1") (pintype "passive"))
      (node (ref "SD_CARD_CONN") (pin "2") (pinfunction "CMD_2") (pintype "bidirectional"))
    )
    (net (code "35") (name "SDDAT0") (class "Default")
      (node (ref "IC1") (pin "66") (pinfunction "PB18_66") (pintype "bidirectional"))
      (node (ref "R9") (pin "1") (pinfunction "1_1") (pintype "passive"))
      (node (ref "SD_CARD_CONN") (pin "7") (pinfunction "DAT0_7") (pintype "bidirectional"))
    )
    (net (code "36") (name "SDDAT1") (class "Default")
      (node (ref "IC1") (pin "67") (pinfunction "PB19_67") (pintype "bidirectional"))
      (node (ref "R10") (pin "1") (pinfunction "1_1") (pintype "passive"))
      (node (ref "SD_CARD_CONN") (pin "8") (pinfunction "DAT1_8") (pintype "bidirectional"))
    )
    (net (code "37") (name "SDDAT2") (class "Default")
      (node (ref "IC1") (pin "68") (pinfunction "PB20_68") (pintype "bidirectional"))
      (node (ref "R11") (pin "1") (pinfunction "1_1") (pintype "passive"))
      (node (ref "SD_CARD_CONN") (pin "9") (pinfunction "DAT2_9") (pintype "bidirectional"))
    )
    (net (code "38") (name "SDDAT3") (class "Default")
      (node (ref "IC1") (pin "69") (pinfunction "PB21_69") (pintype "bidirectional"))
      (node (ref "R7") (pin "1") (pinfunction "1_1") (pintype "passive"))
      (node (ref "SD_CARD_CONN") (pin "1") (pinfunction "DAT3_1") (pintype "bidirectional"))
    )
    (net (code "39") (name "SDWP") (class "Default")
      (node (ref "IC1") (pin "65") (pinfunction "PB17_65") (pintype "bidirectional"))
      (node (ref "R13") (pin "1") (pinfunction "1_1") (pintype "passive"))
      (node (ref "SD_CARD_CONN") (pin "WP1") (pinfunction "WRITE_PROTECT_WP1") (pintype "bidirectional"))
    )
    (net (code "40") (name "SERVO_PWM") (class "Default")
      (node (ref "IC1") (pin "20") (pinfunction "PA07_20") (pintype "bidirectional"))
      (node (ref "SERVO") (pin "1") (pinfunction "1_1") (pintype "passive"))
    )
    (net (code "41") (name "START_BTN") (class "Default")
      (node (ref "IC1") (pin "87") (pinfunction "PA27_87") (pintype "bidirectional"))
      (node (ref "R15") (pin "2") (pinfunction "2_2") (pintype "passive"))
      (node (ref "START_BTN") (pin "1") (pinfunction "COM_1_1") (pintype "bidirectional"))
      (node (ref "START_BTN") (pin "2") (pinfunction "COM_2_2") (pintype "bidirectional"))
    )
    (net (code "42") (name "SWDCLK") (class "Default")
      (node (ref "IC1") (pin "93") (pinfunction "PA30_93") (pintype "bidirectional"))
      (node (ref "PROG") (pin "3") (pinfunction "3_3") (pintype "passive"))
      (node (ref "R14") (pin "1") (pinfunction "1_1") (pintype "passive"))
    )
    (net (code "43") (name "SWDIO") (class "Default")
      (node (ref "IC1") (pin "94") (pinfunction "PA31_94") (pintype "bidirectional"))
      (node (ref "PROG") (pin "4") (pinfunction "4_4") (pintype "passive"))
    )
    (net (code "44") (name "SWO") (class "Default")
      (node (ref "IC1") (pin "95") (pinfunction "PB30_95") (pintype "bidirectional"))
      (node (ref "PROG") (pin "2") (pinfunction "2_2") (pintype "passive"))
    )
    (net (code "45") (name "TRACECLK") (class "Default")
      (node (ref "IC1") (pin "85") (pinfunction "PC27_85") (pintype "bidirectional"))
      (node (ref "PROG") (pin "9") (pinfunction "9_9") (pintype "passive"))
    )
    (net (code "46") (name "TRACEDATA[0]") (class "Default")
      (node (ref "IC1") (pin "86") (pinfunction "PC28_86") (pintype "bidirectional"))
      (node (ref "PROG") (pin "5") (pinfunction "5_5") (pintype "passive"))
    )
    (net (code "47") (name "TRACEDATA[1]") (class "Default")
      (node (ref "IC1") (pin "84") (pinfunction "PC26_84") (pintype "bidirectional"))
      (node (ref "PROG") (pin "6") (pinfunction "6_6") (pintype "passive"))
    )
    (net (code "48") (name "TRACEDATA[2]") (class "Default")
      (node (ref "IC1") (pin "83") (pinfunction "PC25_83") (pintype "bidirectional"))
      (node (ref "PROG") (pin "7") (pinfunction "7_7") (pintype "passive"))
    )
    (net (code "49") (name "TRACEDATA[3]") (class "Default")
      (node (ref "IC1") (pin "82") (pinfunction "PC24_82") (pintype "bidirectional"))
      (node (ref "PROG") (pin "8") (pinfunction "8_8") (pintype "passive"))
    )
    (net (code "50") (name "VDDCORE") (class "Default")
      (node (ref "C11") (pin "1") (pinfunction "1_1") (pintype "passive"))
      (node (ref "C14") (pin "1") (pinfunction "1_1") (pintype "passive"))
      (node (ref "IC1") (pin "89") (pinfunction "VDDCORE_89") (pintype "bidirectional"))
    )
    (net (code "51") (name "XIN1") (class "Default")
      (node (ref "C12") (pin "1") (pinfunction "1_1") (pintype "passive"))
      (node (ref "IC1") (pin "78") (pinfunction "PB22_78") (pintype "bidirectional"))
      (node (ref "OSC1") (pin "1") (pinfunction "1_1") (pintype "bidirectional"))
    )
    (net (code "52") (name "XOUT1") (class "Default")
      (node (ref "C13") (pin "1") (pinfunction "1_1") (pintype "passive"))
      (node (ref "IC1") (pin "79") (pinfunction "PB23_79") (pintype "bidirectional"))
      (node (ref "OSC1") (pin "3") (pinfunction "3_3") (pintype "bidirectional"))
    )
    (net (code "53") (name "unconnected-(IC1-PA00-Pad1)") (class "Default")
      (node (ref "IC1") (pin "1") (pinfunction "PA00_1") (pintype "bidirectional"))
    )
    (net (code "54") (name "unconnected-(IC1-PA01-Pad2)") (class "Default")
      (node (ref "IC1") (pin "2") (pinfunction "PA01_2") (pintype "bidirectional"))
    )
    (net (code "55") (name "unconnected-(IC1-PA02-Pad7)") (class "Default")
      (node (ref "IC1") (pin "7") (pinfunction "PA02_7") (pintype "bidirectional"))
    )
    (net (code "56") (name "unconnected-(IC1-PA03-Pad8)") (class "Default")
      (node (ref "IC1") (pin "8") (pinfunction "PA03_8") (pintype "bidirectional"))
    )
    (net (code "57") (name "unconnected-(IC1-PA08-Pad26)") (class "Default")
      (node (ref "IC1") (pin "26") (pinfunction "PA08_26") (pintype "bidirectional"))
    )
    (net (code "58") (name "unconnected-(IC1-PA09-Pad27)") (class "Default")
      (node (ref "IC1") (pin "27") (pinfunction "PA09_27") (pintype "bidirectional"))
    )
    (net (code "59") (name "unconnected-(IC1-PA10-Pad28)") (class "Default")
      (node (ref "IC1") (pin "28") (pinfunction "PA10_28") (pintype "bidirectional"))
    )
    (net (code "60") (name "unconnected-(IC1-PA11-Pad29)") (class "Default")
      (node (ref "IC1") (pin "29") (pinfunction "PA11_29") (pintype "bidirectional"))
    )
    (net (code "61") (name "unconnected-(IC1-PA12-Pad46)") (class "Default")
      (node (ref "IC1") (pin "46") (pinfunction "PA12_46") (pintype "bidirectional"))
    )
    (net (code "62") (name "unconnected-(IC1-PA13-Pad47)") (class "Default")
      (node (ref "IC1") (pin "47") (pinfunction "PA13_47") (pintype "bidirectional"))
    )
    (net (code "63") (name "unconnected-(IC1-PA14-Pad48)") (class "Default")
      (node (ref "IC1") (pin "48") (pinfunction "PA14_48") (pintype "bidirectional"))
    )
    (net (code "64") (name "unconnected-(IC1-PA15-Pad49)") (class "Default")
      (node (ref "IC1") (pin "49") (pinfunction "PA15_49") (pintype "bidirectional"))
    )
    (net (code "65") (name "unconnected-(IC1-PA16-Pad52)") (class "Default")
      (node (ref "IC1") (pin "52") (pinfunction "PA16_52") (pintype "bidirectional"))
    )
    (net (code "66") (name "unconnected-(IC1-PA17-Pad53)") (class "Default")
      (node (ref "IC1") (pin "53") (pinfunction "PA17_53") (pintype "bidirectional"))
    )
    (net (code "67") (name "unconnected-(IC1-PA18-Pad54)") (class "Default")
      (node (ref "IC1") (pin "54") (pinfunction "PA18_54") (pintype "bidirectional"))
    )
    (net (code "68") (name "unconnected-(IC1-PA19-Pad55)") (class "Default")
      (node (ref "IC1") (pin "55") (pinfunction "PA19_55") (pintype "bidirectional"))
    )
    (net (code "69") (name "unconnected-(IC1-PA22-Pad72)") (class "Default")
      (node (ref "IC1") (pin "72") (pinfunction "PA22_72") (pintype "bidirectional"))
    )
    (net (code "70") (name "unconnected-(IC1-PA23-Pad73)") (class "Default")
      (node (ref "IC1") (pin "73") (pinfunction "PA23_73") (pintype "bidirectional"))
    )
    (net (code "71") (name "unconnected-(IC1-PA24-Pad74)") (class "Default")
      (node (ref "IC1") (pin "74") (pinfunction "PA24_74") (pintype "bidirectional"))
    )
    (net (code "72") (name "unconnected-(IC1-PA25-Pad75)") (class "Default")
      (node (ref "IC1") (pin "75") (pinfunction "PA25_75") (pintype "bidirectional"))
    )
    (net (code "73") (name "unconnected-(IC1-PB00-Pad97)") (class "Default")
      (node (ref "IC1") (pin "97") (pinfunction "PB00_97") (pintype "bidirectional"))
    )
    (net (code "74") (name "unconnected-(IC1-PB01-Pad98)") (class "Default")
      (node (ref "IC1") (pin "98") (pinfunction "PB01_98") (pintype "bidirectional"))
    )
    (net (code "75") (name "unconnected-(IC1-PB02-Pad99)") (class "Default")
      (node (ref "IC1") (pin "99") (pinfunction "PB02_99") (pintype "bidirectional"))
    )
    (net (code "76") (name "unconnected-(IC1-PB03-Pad100)") (class "Default")
      (node (ref "IC1") (pin "100") (pinfunction "PB03_100") (pintype "bidirectional"))
    )
    (net (code "77") (name "unconnected-(IC1-PB04-Pad9)") (class "Default")
      (node (ref "IC1") (pin "9") (pinfunction "PB04_9") (pintype "bidirectional"))
    )
    (net (code "78") (name "unconnected-(IC1-PB05-Pad10)") (class "Default")
      (node (ref "IC1") (pin "10") (pinfunction "PB05_10") (pintype "bidirectional"))
    )
    (net (code "79") (name "unconnected-(IC1-PB06-Pad13)") (class "Default")
      (node (ref "IC1") (pin "13") (pinfunction "PB06_13") (pintype "bidirectional"))
    )
    (net (code "80") (name "unconnected-(IC1-PB07-Pad14)") (class "Default")
      (node (ref "IC1") (pin "14") (pinfunction "PB07_14") (pintype "bidirectional"))
    )
    (net (code "81") (name "unconnected-(IC1-PB08-Pad15)") (class "Default")
      (node (ref "IC1") (pin "15") (pinfunction "PB08_15") (pintype "bidirectional"))
    )
    (net (code "82") (name "unconnected-(IC1-PB10-Pad32)") (class "Default")
      (node (ref "IC1") (pin "32") (pinfunction "PB10_32") (pintype "bidirectional"))
    )
    (net (code "83") (name "unconnected-(IC1-PB11-Pad33)") (class "Default")
      (node (ref "IC1") (pin "33") (pinfunction "PB11_33") (pintype "bidirectional"))
    )
    (net (code "84") (name "unconnected-(IC1-PB12-Pad34)") (class "Default")
      (node (ref "IC1") (pin "34") (pinfunction "PB12_34") (pintype "bidirectional"))
    )
    (net (code "85") (name "unconnected-(IC1-PB13-Pad35)") (class "Default")
      (node (ref "IC1") (pin "35") (pinfunction "PB13_35") (pintype "bidirectional"))
    )
    (net (code "86") (name "unconnected-(IC1-PB14-Pad36)") (class "Default")
      (node (ref "IC1") (pin "36") (pinfunction "PB14_36") (pintype "bidirectional"))
    )
    (net (code "87") (name "unconnected-(IC1-PB15-Pad37)") (class "Default")
      (node (ref "IC1") (pin "37") (pinfunction "PB15_37") (pintype "bidirectional"))
    )
    (net (code "88") (name "unconnected-(IC1-PB24-Pad80)") (class "Default")
      (node (ref "IC1") (pin "80") (pinfunction "PB24_80") (pintype "bidirectional"))
    )
    (net (code "89") (name "unconnected-(IC1-PB25-Pad81)") (class "Default")
      (node (ref "IC1") (pin "81") (pinfunction "PB25_81") (pintype "bidirectional"))
    )
    (net (code "90") (name "unconnected-(IC1-PB31-Pad96)") (class "Default")
      (node (ref "IC1") (pin "96") (pinfunction "PB31_96") (pintype "bidirectional"))
    )
    (net (code "91") (name "unconnected-(IC1-PC00-Pad3)") (class "Default")
      (node (ref "IC1") (pin "3") (pinfunction "PC00_3") (pintype "bidirectional"))
    )
    (net (code "92") (name "unconnected-(IC1-PC01-Pad4)") (class "Default")
      (node (ref "IC1") (pin "4") (pinfunction "PC01_4") (pintype "bidirectional"))
    )
    (net (code "93") (name "unconnected-(IC1-PC02-Pad5)") (class "Default")
      (node (ref "IC1") (pin "5") (pinfunction "PC02_5") (pintype "bidirectional"))
    )
    (net (code "94") (name "unconnected-(IC1-PC03-Pad6)") (class "Default")
      (node (ref "IC1") (pin "6") (pinfunction "PC03_6") (pintype "bidirectional"))
    )
    (net (code "95") (name "unconnected-(IC1-PC05-Pad21)") (class "Default")
      (node (ref "IC1") (pin "21") (pinfunction "PC05_21") (pintype "bidirectional"))
    )
    (net (code "96") (name "unconnected-(IC1-PC06-Pad22)") (class "Default")
      (node (ref "IC1") (pin "22") (pinfunction "PC06_22") (pintype "bidirectional"))
    )
    (net (code "97") (name "unconnected-(IC1-PC07-Pad23)") (class "Default")
      (node (ref "IC1") (pin "23") (pinfunction "PC07_23") (pintype "bidirectional"))
    )
    (net (code "98") (name "unconnected-(IC1-PC10-Pad40)") (class "Default")
      (node (ref "IC1") (pin "40") (pinfunction "PC10_40") (pintype "bidirectional"))
    )
    (net (code "99") (name "unconnected-(IC1-PC11-Pad41)") (class "Default")
      (node (ref "IC1") (pin "41") (pinfunction "PC11_41") (pintype "bidirectional"))
    )
    (net (code "100") (name "unconnected-(IC1-PC12-Pad42)") (class "Default")
      (node (ref "IC1") (pin "42") (pinfunction "PC12_42") (pintype "bidirectional"))
    )
    (net (code "101") (name "unconnected-(IC1-PC13-Pad43)") (class "Default")
      (node (ref "IC1") (pin "43") (pinfunction "PC13_43") (pintype "bidirectional"))
    )
    (net (code "102") (name "unconnected-(IC1-PC14-Pad44)") (class "Default")
      (node (ref "IC1") (pin "44") (pinfunction "PC14_44") (pintype "bidirectional"))
    )
    (net (code "103") (name "unconnected-(IC1-PC15-Pad45)") (class "Default")
      (node (ref "IC1") (pin "45") (pinfunction "PC15_45") (pintype "bidirectional"))
    )
    (net (code "104") (name "unconnected-(IC1-PC16-Pad56)") (class "Default")
      (node (ref "IC1") (pin "56") (pinfunction "PC16_56") (pintype "bidirectional"))
    )
    (net (code "105") (name "unconnected-(IC1-PC17-Pad57)") (class "Default")
      (node (ref "IC1") (pin "57") (pinfunction "PC17_57") (pintype "bidirectional"))
    )
    (net (code "106") (name "unconnected-(IC1-PC18-Pad58)") (class "Default")
      (node (ref "IC1") (pin "58") (pinfunction "PC18_58") (pintype "bidirectional"))
    )
    (net (code "107") (name "unconnected-(IC1-PC19-Pad59)") (class "Default")
      (node (ref "IC1") (pin "59") (pinfunction "PC19_59") (pintype "bidirectional"))
    )
    (net (code "108") (name "unconnected-(IC1-PC20-Pad60)") (class "Default")
      (node (ref "IC1") (pin "60") (pinfunction "PC20_60") (pintype "bidirectional"))
    )
    (net (code "109") (name "unconnected-(IC1-PC21-Pad61)") (class "Default")
      (node (ref "IC1") (pin "61") (pinfunction "PC21_61") (pintype "bidirectional"))
    )
    (net (code "110") (name "unconnected-(IC1-VSW-Pad91)") (class "Default")
      (node (ref "IC1") (pin "91") (pinfunction "VSW_91") (pintype "bidirectional"))
    )
    (net (code "111") (name "unconnected-(OSC1-Pad2)") (class "Default")
      (node (ref "OSC1") (pin "2") (pinfunction "2_2") (pintype "no_connect"))
    )
    (net (code "112") (name "unconnected-(OSC1-Pad4)") (class "Default")
      (node (ref "OSC1") (pin "4") (pinfunction "4_4") (pintype "no_connect"))
    )
  )
)
